# SCH_PCB-ROCKET-1_2024-07-06.net
KiCad netlist of a schematic drawn in EasyEDA
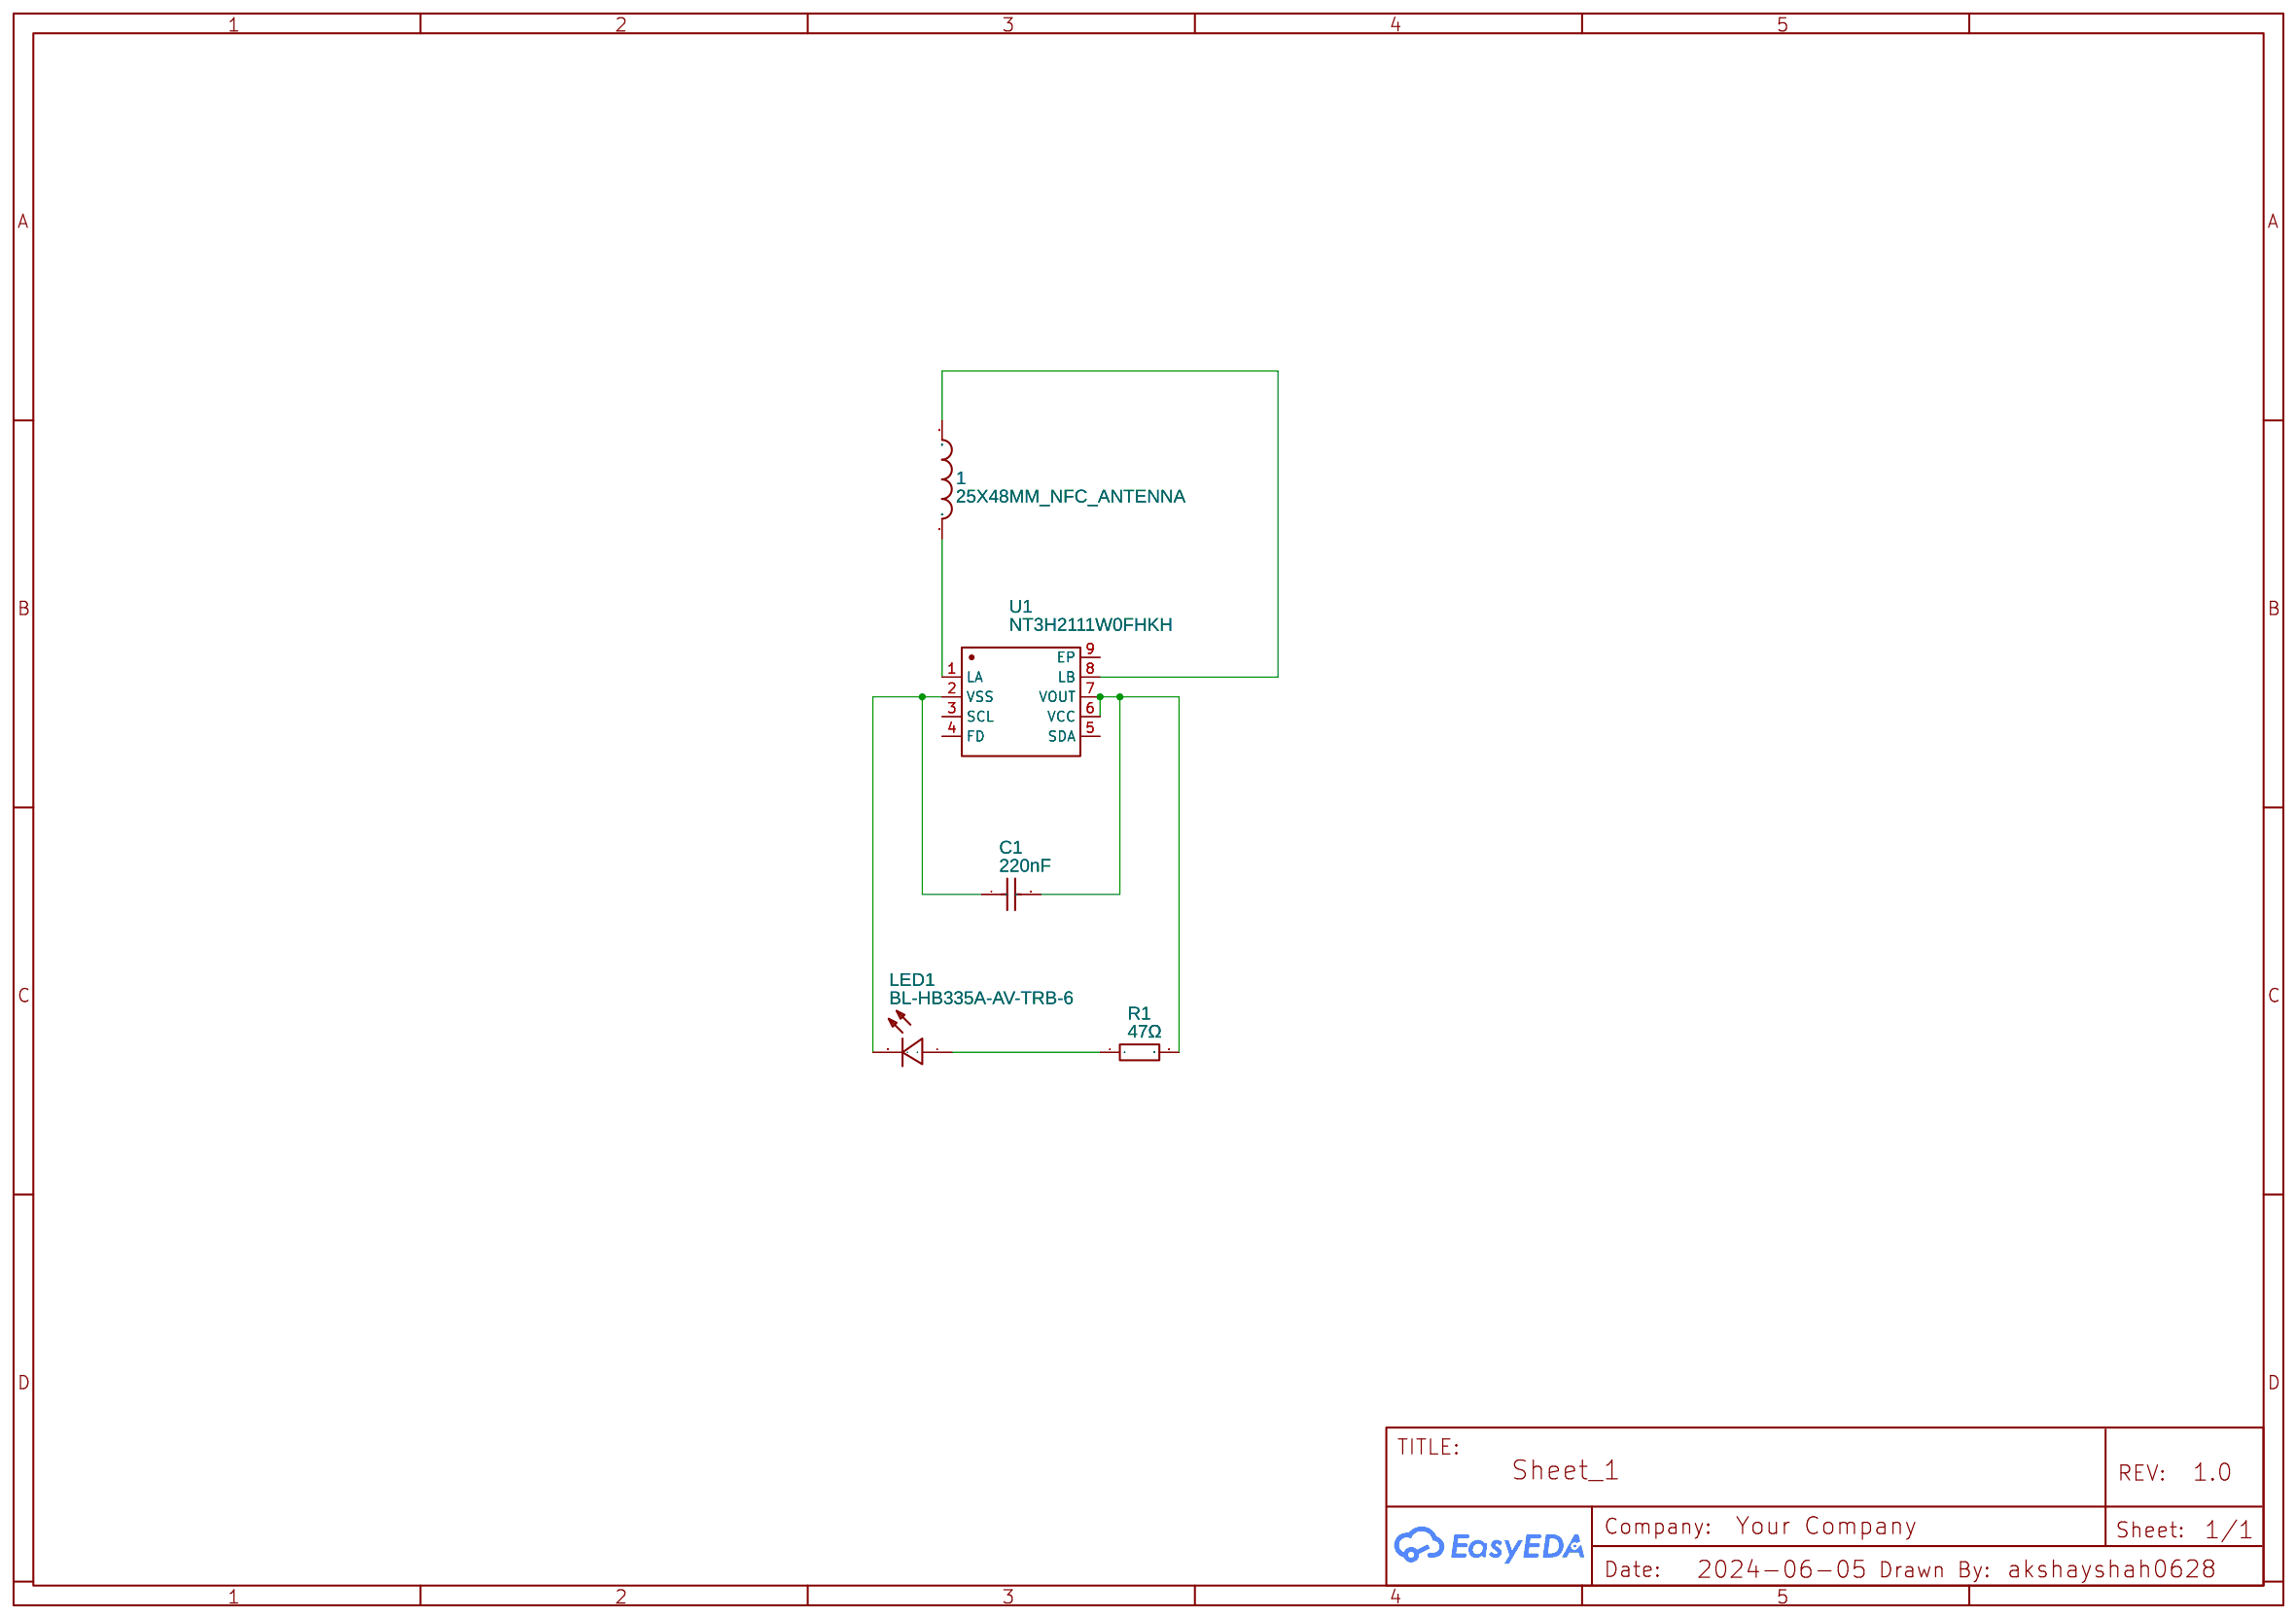
[diagram p0: schematic sheet]

(export (version "E")
  (design (tool "Eeschema 10.0.6"))
  (components
    (comp (ref "1") (value "25X48MM_NFC_ANTENNA") (libsource (lib "") (part "25X48MM_NFC_ANTENNA")))
    (comp (ref "C1")
      (value "220nF")
      (fields
        (field (name "Manufacturer Part") "CL10B224KA8NNNC")
        (field (name "Manufacturer") "SAMSUNG(三星)")
      )
      (libsource (lib "") (part "CL10B224KA8NNNC"))
    )
    (comp (ref "LED1")
      (value "BL-HB335A-AV-TRB-6")
      (fields (field (name "Manufacturer") "BrtLed(佰鸿)"))
      (libsource (lib "") (part "BL-HB335A-AV-TRB-6"))
    )
    (comp (ref "R1")
      (value "47Ω")
      (fields
        (field (name "Manufacturer Part") "0603WAF470JT5E")
        (field (name "Manufacturer") "UNI-ROYAL(厚声)")
      )
      (libsource (lib "") (part "0603WAF470JT5E"))
    )
    (comp (ref "U1")
      (value "NT3H2111W0FHKH")
      (fields (field (name "Manufacturer") "NXP(恩智浦)"))
      (libsource (lib "") (part "NT3H2111W0FHKH"))
    )
  )
  (nets
    (net (code "1") (name "Net-(LED1-+)") (class "Default")
      (node (ref "LED1") (pin "1") (pinfunction "+_1") (pintype "unspecified"))
      (node (ref "R1") (pin "1") (pinfunction "1_1") (pintype "input"))
    )
    (net (code "2") (name "Net-(LED1--)") (class "Default")
      (node (ref "C1") (pin "1") (pinfunction "1_1") (pintype "input"))
      (node (ref "LED1") (pin "2") (pinfunction "-_2") (pintype "unspecified"))
      (node (ref "U1") (pin "2") (pinfunction "VSS_2") (pintype "unspecified"))
    )
    (net (code "3") (name "Net-(U1-LA)") (class "Default")
      (node (ref "1") (pin "P$2") (pinfunction "P$2_P$2") (pintype "bidirectional"))
      (node (ref "U1") (pin "1") (pinfunction "LA_1") (pintype "unspecified"))
    )
    (net (code "4") (name "Net-(U1-LB)") (class "Default")
      (node (ref "1") (pin "P$1") (pinfunction "P$1_P$1") (pintype "bidirectional"))
      (node (ref "U1") (pin "8") (pinfunction "LB_8") (pintype "unspecified"))
    )
    (net (code "5") (name "Net-(U1-VCC)") (class "Default")
      (node (ref "C1") (pin "2") (pinfunction "2_2") (pintype "input"))
      (node (ref "R1") (pin "2") (pinfunction "2_2") (pintype "input"))
      (node (ref "U1") (pin "6") (pinfunction "VCC_6") (pintype "unspecified"))
      (node (ref "U1") (pin "7") (pinfunction "VOUT_7") (pintype "unspecified"))
    )
    (net (code "6") (name "unconnected-(U1-EP-Pad9)") (class "Default")
      (node (ref "U1") (pin "9") (pinfunction "EP_9") (pintype "unspecified"))
    )
    (net (code "7") (name "unconnected-(U1-FD-Pad4)") (class "Default")
      (node (ref "U1") (pin "4") (pinfunction "FD_4") (pintype "unspecified"))
    )
    (net (code "8") (name "unconnected-(U1-SCL-Pad3)") (class "Default")
      (node (ref "U1") (pin "3") (pinfunction "SCL_3") (pintype "unspecified"))
    )
    (net (code "9") (name "unconnected-(U1-SDA-Pad5)") (class "Default")
      (node (ref "U1") (pin "5") (pinfunction "SDA_5") (pintype "unspecified"))
    )
  )
)
